# SD2DIPSPI.net
KiCad netlist of a schematic drawn in EAGLE
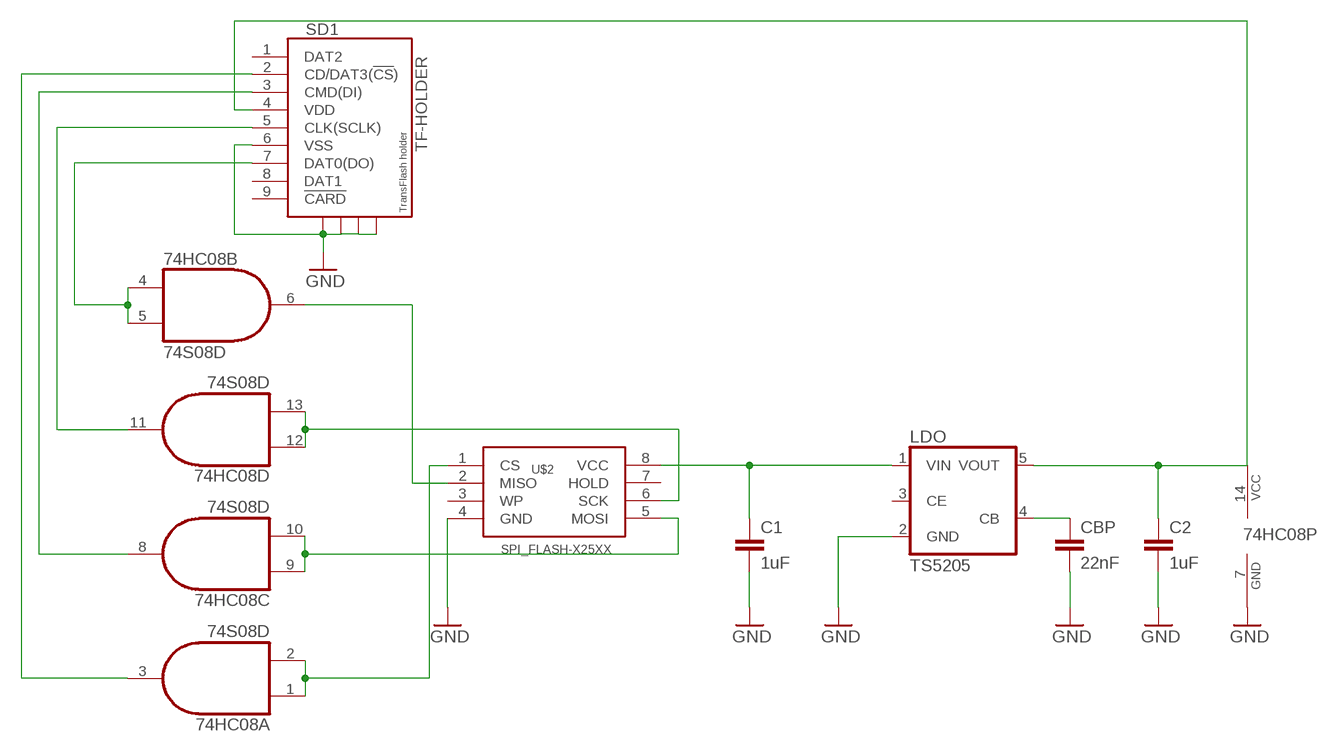
[diagram p0: schematic, sheet 1]

(export (version "E")
  (design (tool "Eeschema 10.0.6"))
  (components
    (comp (ref "74HC08")
      (value "74S08D")
      (footprint "eagle-import:SO14")
      (libsource (lib "eagle-import") (part "7408DS"))
    )
    (comp (ref "C1")
      (value "1uF")
      (footprint "eagle-import:0603-CAP")
      (libsource (lib "eagle-import") (part "0.1UF-25V(+80/-20%)(0603)"))
    )
    (comp (ref "C2")
      (value "1uF")
      (footprint "eagle-import:0603-CAP")
      (libsource (lib "eagle-import") (part "0.1UF-25V(+80/-20%)(0603)"))
    )
    (comp (ref "CBP")
      (value "22nF")
      (footprint "eagle-import:0402-CAP")
      (libsource (lib "eagle-import") (part "0.1UF-16V(+-10%)(0402)"))
    )
    (comp (ref "LDO")
      (value "TS5205")
      (footprint "eagle-import:SOT25")
      (libsource (lib "eagle-import") (part "TS5205"))
    )
    (comp (ref "SD1")
      (value "TF-HOLDER")
      (footprint "eagle-import:TF-PULL")
      (libsource (lib "eagle-import") (part "TF-HOLDER"))
    )
    (comp (ref "U$2")
      (value "SPI_FLASH-X25XX")
      (footprint "eagle-import:DIL08")
      (libsource (lib "eagle-import") (part "SPI_FLASH-X25XX"))
    )
  )
  (nets
    (net (code "1") (name "GND") (class "Default")
      (node (ref "74HC08") (pin "7") (pinfunction "GND_7") (pintype "power_in"))
      (node (ref "C1") (pin "2") (pinfunction "2_2") (pintype "passive"))
      (node (ref "C2") (pin "2") (pinfunction "2_2") (pintype "passive"))
      (node (ref "CBP") (pin "2") (pinfunction "2_2") (pintype "passive"))
      (node (ref "LDO") (pin "2") (pinfunction "GND_2") (pintype "passive"))
      (node (ref "SD1") (pin "6") (pinfunction "VSS_6") (pintype "power_in"))
      (node (ref "SD1") (pin "S1") (pinfunction "S1_S1") (pintype "passive"))
      (node (ref "SD1") (pin "S2") (pinfunction "S2_S2") (pintype "passive"))
      (node (ref "SD1") (pin "S3") (pinfunction "S3_S3") (pintype "passive"))
      (node (ref "SD1") (pin "S4") (pinfunction "S4_S4") (pintype "passive"))
      (node (ref "U$2") (pin "4") (pinfunction "GND_4") (pintype "bidirectional"))
    )
    (net (code "2") (name "Net-(74HC08A-I0)") (class "Default")
      (node (ref "74HC08") (pin "1") (pinfunction "I0_1") (pintype "input"))
      (node (ref "74HC08") (pin "2") (pinfunction "I1_2") (pintype "input"))
      (node (ref "U$2") (pin "1") (pinfunction "CS_1") (pintype "bidirectional"))
    )
    (net (code "3") (name "Net-(74HC08A-O)") (class "Default")
      (node (ref "74HC08") (pin "3") (pinfunction "O_3") (pintype "output"))
      (node (ref "SD1") (pin "2") (pinfunction "CD/DAT3(~{CS})_2") (pintype "bidirectional"))
    )
    (net (code "4") (name "Net-(74HC08B-I0)") (class "Default")
      (node (ref "74HC08") (pin "4") (pinfunction "I0_4") (pintype "input"))
      (node (ref "74HC08") (pin "5") (pinfunction "I1_5") (pintype "input"))
      (node (ref "SD1") (pin "7") (pinfunction "DAT0(DO)_7") (pintype "bidirectional"))
    )
    (net (code "5") (name "Net-(74HC08B-O)") (class "Default")
      (node (ref "74HC08") (pin "6") (pinfunction "O_6") (pintype "output"))
      (node (ref "U$2") (pin "2") (pinfunction "MISO_2") (pintype "bidirectional"))
    )
    (net (code "6") (name "Net-(74HC08C-I0)") (class "Default")
      (node (ref "74HC08") (pin "10") (pinfunction "I1_10") (pintype "input"))
      (node (ref "74HC08") (pin "9") (pinfunction "I0_9") (pintype "input"))
      (node (ref "U$2") (pin "5") (pinfunction "MOSI_5") (pintype "bidirectional"))
    )
    (net (code "7") (name "Net-(74HC08C-O)") (class "Default")
      (node (ref "74HC08") (pin "8") (pinfunction "O_8") (pintype "output"))
      (node (ref "SD1") (pin "3") (pinfunction "CMD(DI)_3") (pintype "bidirectional"))
    )
    (net (code "8") (name "Net-(74HC08D-I0)") (class "Default")
      (node (ref "74HC08") (pin "12") (pinfunction "I0_12") (pintype "input"))
      (node (ref "74HC08") (pin "13") (pinfunction "I1_13") (pintype "input"))
      (node (ref "U$2") (pin "6") (pinfunction "SCK_6") (pintype "bidirectional"))
    )
    (net (code "9") (name "Net-(74HC08D-O)") (class "Default")
      (node (ref "74HC08") (pin "11") (pinfunction "O_11") (pintype "output"))
      (node (ref "SD1") (pin "5") (pinfunction "CLK(SCLK)_5") (pintype "input"))
    )
    (net (code "10") (name "Net-(74HC08E-VCC)") (class "Default")
      (node (ref "74HC08") (pin "14") (pinfunction "VCC_14") (pintype "power_in"))
      (node (ref "C2") (pin "1") (pinfunction "1_1") (pintype "passive"))
      (node (ref "LDO") (pin "5") (pinfunction "VOUT_5") (pintype "passive"))
      (node (ref "SD1") (pin "4") (pinfunction "VDD_4") (pintype "power_in"))
    )
    (net (code "11") (name "Net-(LDO-CB)") (class "Default")
      (node (ref "CBP") (pin "1") (pinfunction "1_1") (pintype "passive"))
      (node (ref "LDO") (pin "4") (pinfunction "CB_4") (pintype "input"))
    )
    (net (code "12") (name "Net-(LDO-VIN)") (class "Default")
      (node (ref "C1") (pin "1") (pinfunction "1_1") (pintype "passive"))
      (node (ref "LDO") (pin "1") (pinfunction "VIN_1") (pintype "input"))
      (node (ref "U$2") (pin "8") (pinfunction "VCC_8") (pintype "bidirectional"))
    )
    (net (code "13") (name "unconnected-(LDO-CE-Pad3)") (class "Default")
      (node (ref "LDO") (pin "3") (pinfunction "CE_3") (pintype "input"))
    )
    (net (code "14") (name "unconnected-(SD1-DAT1-Pad8)") (class "Default")
      (node (ref "SD1") (pin "8") (pinfunction "DAT1_8") (pintype "bidirectional"))
    )
    (net (code "15") (name "unconnected-(SD1-DAT2-Pad1)") (class "Default")
      (node (ref "SD1") (pin "1") (pinfunction "DAT2_1") (pintype "bidirectional"))
    )
    (net (code "16") (name "unconnected-(SD1-~{CARD}-Pad9)") (class "Default")
      (node (ref "SD1") (pin "9") (pinfunction "~{CARD}_9") (pintype "passive"))
    )
    (net (code "17") (name "unconnected-(U$2-HOLD-Pad7)") (class "Default")
      (node (ref "U$2") (pin "7") (pinfunction "HOLD_7") (pintype "bidirectional"))
    )
    (net (code "18") (name "unconnected-(U$2-WP-Pad3)") (class "Default")
      (node (ref "U$2") (pin "3") (pinfunction "WP_3") (pintype "bidirectional"))
    )
  )
)
